# IMU.net
KiCad netlist of a schematic drawn in Altium Designer
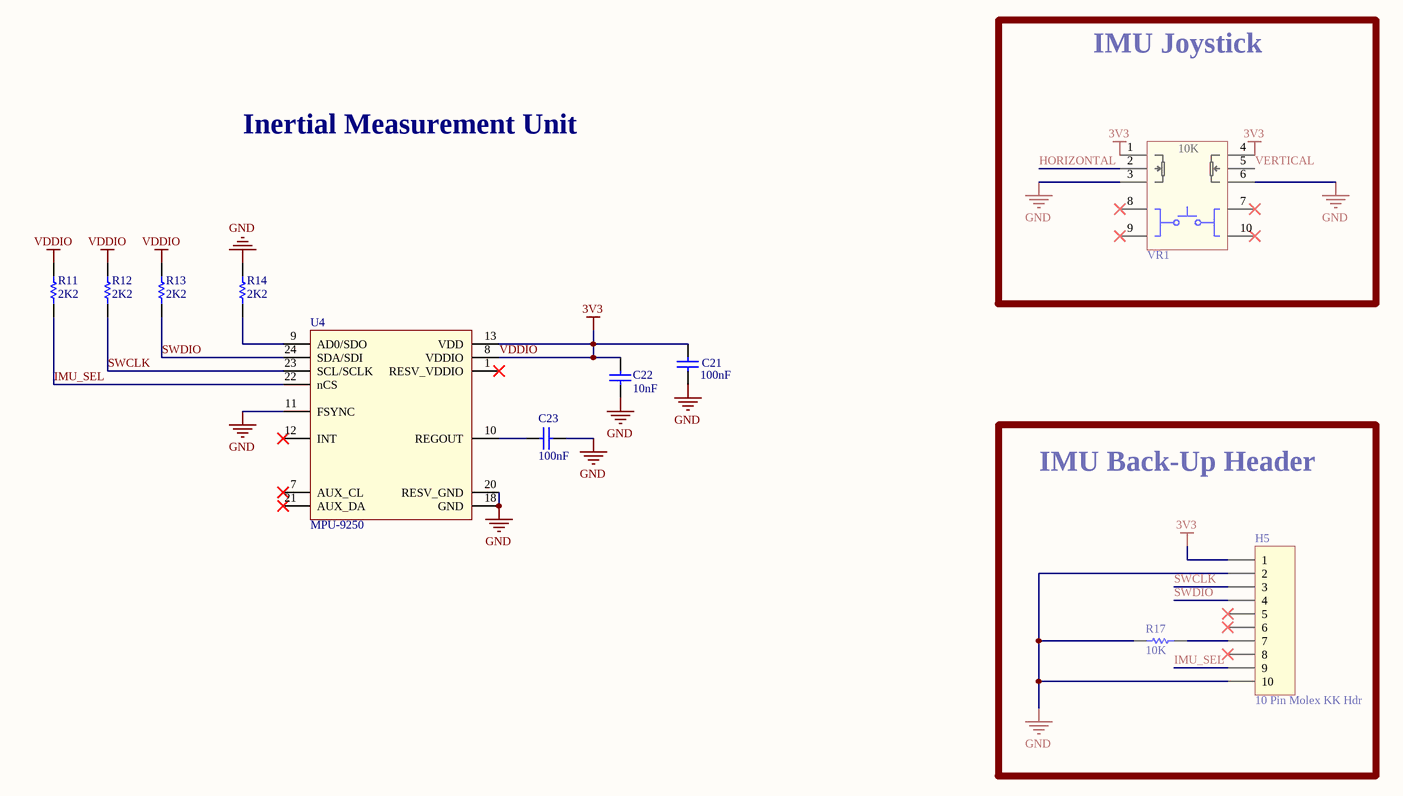
[diagram p0: IMU.SchDoc]

(export (version "E")
  (design (tool "Eeschema 10.0.6"))
  (components
    (comp (ref "C21")
      (value "100nF")
      (footprint "CAPC1608L")
      (description "CAP CER 100nF X7R +-10% 50V 0603")
      (libsource (lib "ECE AD19Components_19V1") (part "CC_100nF_0603"))
    )
    (comp (ref "C22")
      (value "10nF")
      (footprint "CAPC1608L")
      (description "CAP CER 10nF X7R +-10% 50V 0603")
      (libsource (lib "ECE AD19Components_19V1") (part "CC_10nF_0603"))
    )
    (comp (ref "C23")
      (value "100nF")
      (footprint "CAPC1608L")
      (description "CAP CER 100nF X7R +-10% 50V 0603")
      (libsource (lib "ECE AD19Components_19V1") (part "CC_100nF_0603"))
    )
    (comp (ref "H5")
      (value "10 Pin Molex KK Hdr")
      (footprint "MOLEX_KK_10_HDR")
      (description "CONN HEADER 10POS 2.54mm VERT_ Thru Hole")
      (libsource (lib "ECE AD19Components_19V1") (part "JA_MOLEX_KK_10POS"))
    )
    (comp (ref "R11")
      (value "2K2")
      (footprint "RESC1608L")
      (description "RES 2.2K OHM 1/10W 5% 0603 SMD")
      (libsource (lib "ECE AD19Components_19V1") (part "RS_2K2"))
    )
    (comp (ref "R12")
      (value "2K2")
      (footprint "RESC1608L")
      (description "RES 2.2K OHM 1/10W 5% 0603 SMD")
      (libsource (lib "ECE AD19Components_19V1") (part "RS_2K2"))
    )
    (comp (ref "R13")
      (value "2K2")
      (footprint "RESC1608L")
      (description "RES 2.2K OHM 1/10W 5% 0603 SMD")
      (libsource (lib "ECE AD19Components_19V1") (part "RS_2K2"))
    )
    (comp (ref "R14")
      (value "2K2")
      (footprint "RESC1608L")
      (description "RES 2.2K OHM 1/10W 5% 0603 SMD")
      (libsource (lib "ECE AD19Components_19V1") (part "RS_2K2"))
    )
    (comp (ref "R17")
      (value "10K")
      (footprint "RESC1608L")
      (description "RES 10.0K OHM 1/10W 5% 0603 SMD")
      (libsource (lib "ECE AD19Components_19V1") (part "RS_10K"))
    )
    (comp (ref "U4")
      (value "MPU-9250")
      (footprint "Quad24")
      (description "9 axis IMU")
      (libsource (lib "ENCE461AD19_19V2") (part "MPU-9250"))
    )
    (comp (ref "VR1")
      (value "Joystick 10k with Sw")
      (footprint "Joystick_Sw")
      (description "JOYSTICK 10K OHM 2 AXIS TH")
      (libsource (lib "ENCE461AD19_19V2") (part "Joystick 10k with Sw"))
    )
  )
  (nets
    (net (code "1") (name "/HORIZONTAL") (class "Default")
      (node (ref "VR1") (pin "2") (pinfunction "2_2") (pintype "passive"))
    )
    (net (code "2") (name "/IMU_SEL") (class "Default")
      (node (ref "H5") (pin "9") (pinfunction "9_9") (pintype "passive"))
      (node (ref "R11") (pin "1") (pinfunction "1_1") (pintype "passive"))
      (node (ref "U4") (pin "22") (pinfunction "nCS_22") (pintype "passive"))
    )
    (net (code "3") (name "/SWCLK") (class "Default")
      (node (ref "H5") (pin "3") (pinfunction "3_3") (pintype "passive"))
      (node (ref "R12") (pin "1") (pinfunction "1_1") (pintype "passive"))
      (node (ref "U4") (pin "23") (pinfunction "SCL/SCLK_23") (pintype "passive"))
    )
    (net (code "4") (name "/SWDIO") (class "Default")
      (node (ref "H5") (pin "4") (pinfunction "4_4") (pintype "passive"))
      (node (ref "R13") (pin "1") (pinfunction "1_1") (pintype "passive"))
      (node (ref "U4") (pin "24") (pinfunction "SDA/SDI_24") (pintype "passive"))
    )
    (net (code "5") (name "/VERTICAL") (class "Default")
      (node (ref "VR1") (pin "5") (pinfunction "2'_5") (pintype "passive"))
    )
    (net (code "6") (name "3V3") (class "Default")
      (node (ref "C21") (pin "2") (pinfunction "2_2") (pintype "passive"))
      (node (ref "C22") (pin "2") (pinfunction "2_2") (pintype "passive"))
      (node (ref "H5") (pin "1") (pinfunction "1_1") (pintype "passive"))
      (node (ref "R11") (pin "2") (pinfunction "2_2") (pintype "passive"))
      (node (ref "R12") (pin "2") (pinfunction "2_2") (pintype "passive"))
      (node (ref "R13") (pin "2") (pinfunction "2_2") (pintype "passive"))
      (node (ref "U4") (pin "13") (pinfunction "VDD_13") (pintype "passive"))
      (node (ref "U4") (pin "8") (pinfunction "VDDIO_8") (pintype "passive"))
      (node (ref "VR1") (pin "1") (pinfunction "1_1") (pintype "passive"))
      (node (ref "VR1") (pin "4") (pinfunction "1'_4") (pintype "passive"))
    )
    (net (code "7") (name "GND") (class "Default")
      (node (ref "C21") (pin "1") (pinfunction "1_1") (pintype "passive"))
      (node (ref "C22") (pin "1") (pinfunction "1_1") (pintype "passive"))
      (node (ref "C23") (pin "2") (pinfunction "2_2") (pintype "passive"))
      (node (ref "H5") (pin "10") (pinfunction "10_10") (pintype "passive"))
      (node (ref "H5") (pin "2") (pinfunction "2_2") (pintype "passive"))
      (node (ref "R14") (pin "2") (pinfunction "2_2") (pintype "passive"))
      (node (ref "R17") (pin "1") (pinfunction "1_1") (pintype "passive"))
      (node (ref "U4") (pin "11") (pinfunction "FSYNC_11") (pintype "passive"))
      (node (ref "U4") (pin "18") (pinfunction "GND_18") (pintype "passive"))
      (node (ref "U4") (pin "20") (pinfunction "RESV_GND_20") (pintype "passive"))
      (node (ref "VR1") (pin "3") (pinfunction "3_3") (pintype "passive"))
      (node (ref "VR1") (pin "6") (pinfunction "3'_6") (pintype "passive"))
    )
    (net (code "8") (name "Net-(H5-Pad7)") (class "Default")
      (node (ref "H5") (pin "7") (pinfunction "7_7") (pintype "passive"))
      (node (ref "R17") (pin "2") (pinfunction "2_2") (pintype "passive"))
    )
    (net (code "9") (name "Net-(U4-AD0{slash}SDO)") (class "Default")
      (node (ref "R14") (pin "1") (pinfunction "1_1") (pintype "passive"))
      (node (ref "U4") (pin "9") (pinfunction "AD0/SDO_9") (pintype "passive"))
    )
    (net (code "10") (name "Net-(U4-REGOUT)") (class "Default")
      (node (ref "C23") (pin "1") (pinfunction "1_1") (pintype "passive"))
      (node (ref "U4") (pin "10") (pinfunction "REGOUT_10") (pintype "passive"))
    )
    (net (code "11") (name "unconnected-(H5-Pad5)") (class "Default")
      (node (ref "H5") (pin "5") (pinfunction "5_5") (pintype "passive+no_connect"))
    )
    (net (code "12") (name "unconnected-(H5-Pad6)") (class "Default")
      (node (ref "H5") (pin "6") (pinfunction "6_6") (pintype "passive+no_connect"))
    )
    (net (code "13") (name "unconnected-(H5-Pad8)") (class "Default")
      (node (ref "H5") (pin "8") (pinfunction "8_8") (pintype "passive+no_connect"))
    )
    (net (code "14") (name "unconnected-(U4-AUX_CL-Pad7)") (class "Default")
      (node (ref "U4") (pin "7") (pinfunction "AUX_CL_7") (pintype "passive+no_connect"))
    )
    (net (code "15") (name "unconnected-(U4-AUX_DA-Pad21)") (class "Default")
      (node (ref "U4") (pin "21") (pinfunction "AUX_DA_21") (pintype "passive+no_connect"))
    )
    (net (code "16") (name "unconnected-(U4-INT-Pad12)") (class "Default")
      (node (ref "U4") (pin "12") (pinfunction "INT_12") (pintype "passive+no_connect"))
    )
    (net (code "17") (name "unconnected-(U4-RESV_VDDIO-Pad1)") (class "Default")
      (node (ref "U4") (pin "1") (pinfunction "RESV_VDDIO_1") (pintype "passive+no_connect"))
    )
    (net (code "18") (name "unconnected-(VR1-Pad7)") (class "Default")
      (node (ref "VR1") (pin "7") (pinfunction "7_7") (pintype "passive+no_connect"))
    )
    (net (code "19") (name "unconnected-(VR1-Pad8)") (class "Default")
      (node (ref "VR1") (pin "8") (pinfunction "8_8") (pintype "passive+no_connect"))
    )
    (net (code "20") (name "unconnected-(VR1-Pad9)") (class "Default")
      (node (ref "VR1") (pin "9") (pinfunction "9_9") (pintype "passive+no_connect"))
    )
    (net (code "21") (name "unconnected-(VR1-Pad10)") (class "Default")
      (node (ref "VR1") (pin "10") (pinfunction "10_10") (pintype "passive+no_connect"))
    )
  )
)
